# MEGA_MSX.net
KiCad netlist of a schematic drawn in EAGLE
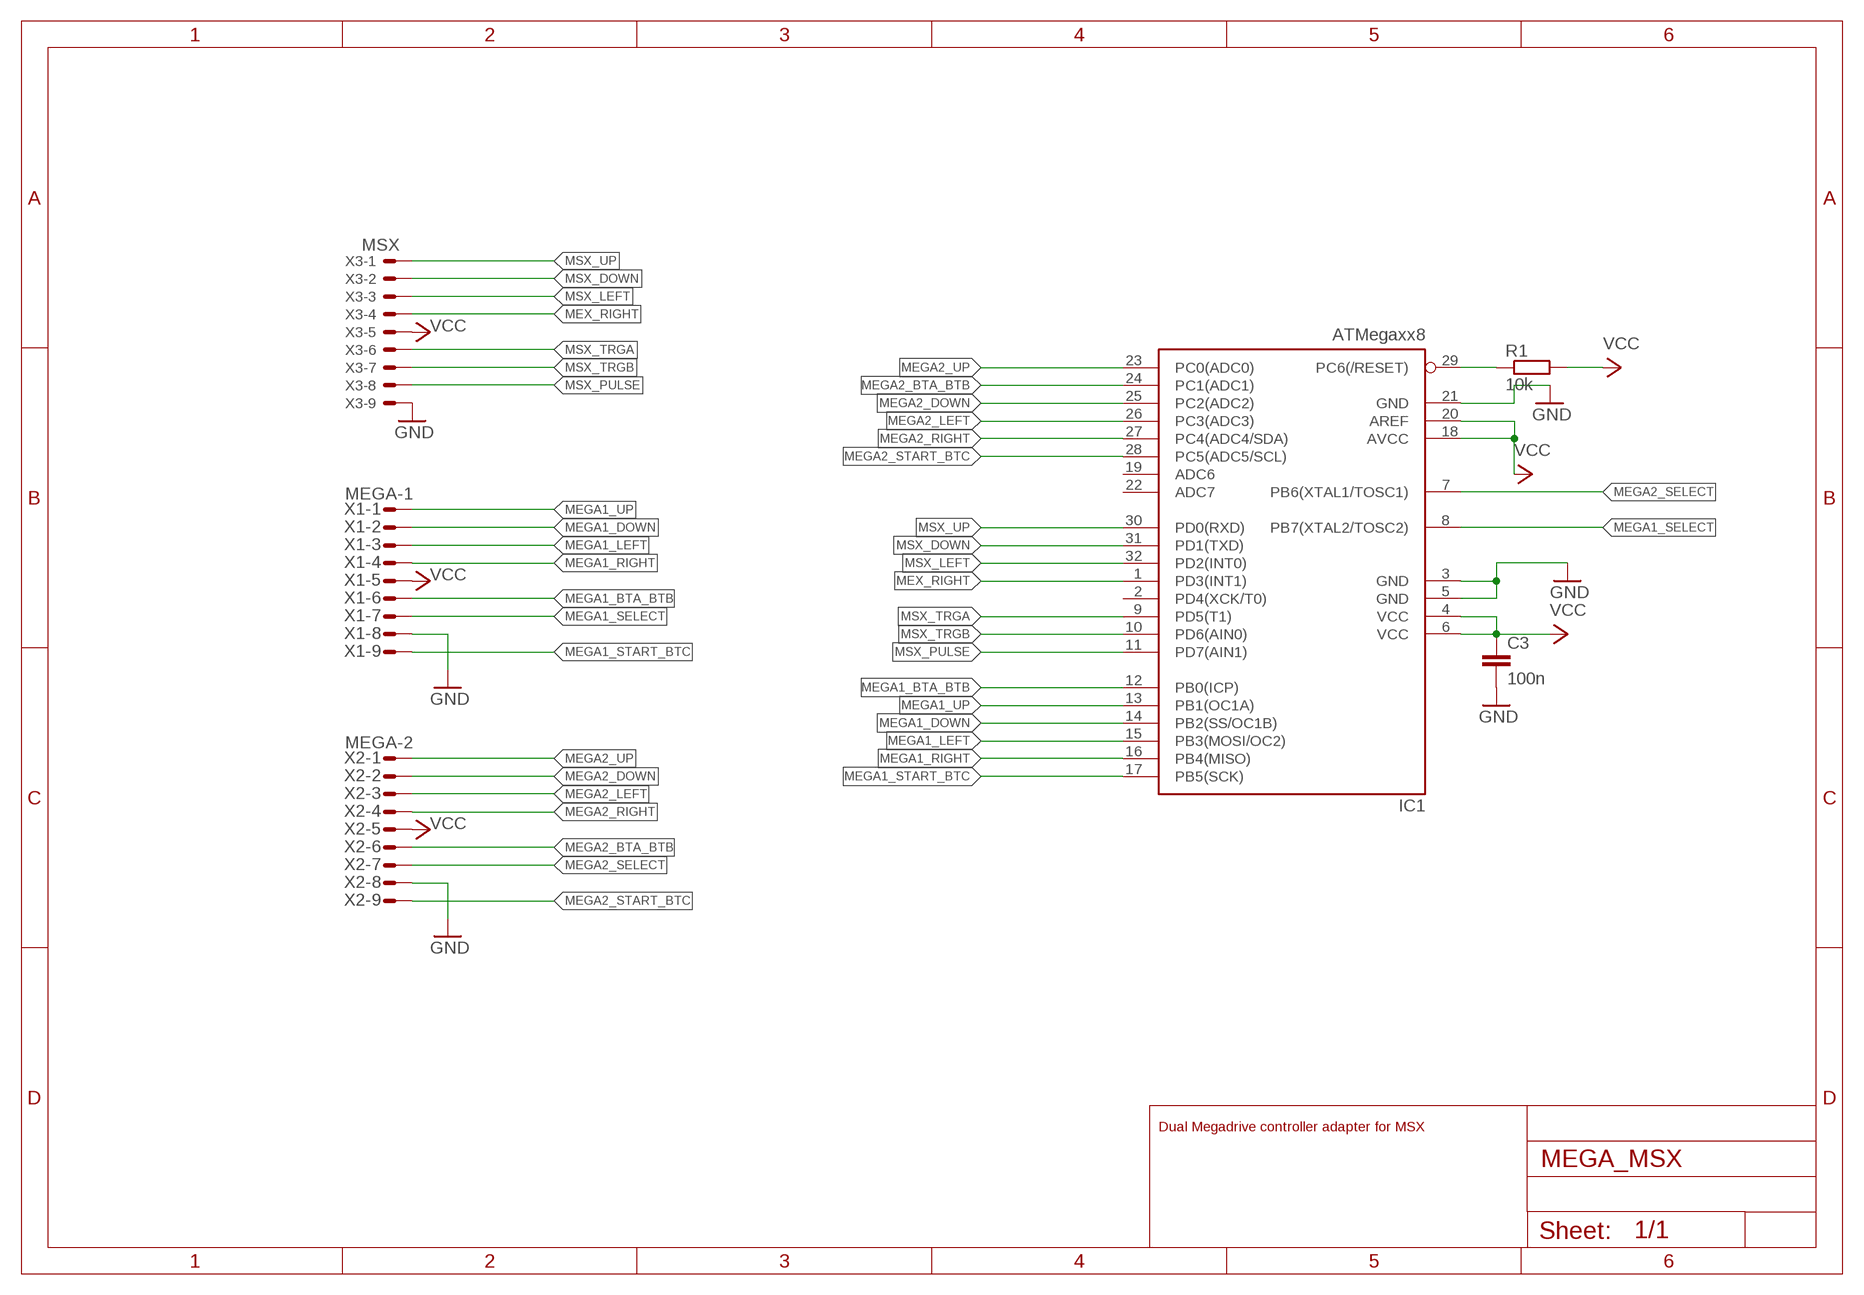
[diagram p0: schematic, sheet 1]

(export (version "E")
  (design (tool "Eeschema 10.0.6"))
  (components
    (comp (ref "C3")
      (value "100n")
      (footprint "eagle-import:C0805")
      (libsource (lib "eagle-import") (part "C-EUC0805"))
    )
    (comp (ref "IC1")
      (value "ATMegaxx8")
      (footprint "eagle-import:TQFP32-08")
      (fields (field (name "MPN") "ATMEGA8-16AU"))
      (libsource (lib "eagle-import") (part "MEGA8-AI"))
    )
    (comp (ref "R1")
      (value "10k")
      (footprint "eagle-import:R0805")
      (libsource (lib "eagle-import") (part "R-EU_R0805"))
    )
    (comp (ref "X1")
      (value "MEGA-1")
      (footprint "eagle-import:M09D")
      (libsource (lib "eagle-import") (part "M09?SD"))
    )
    (comp (ref "X2")
      (value "MEGA-2")
      (footprint "eagle-import:M09D")
      (libsource (lib "eagle-import") (part "M09?SD"))
    )
    (comp (ref "X3")
      (value "MSX")
      (footprint "eagle-import:22-23-2091")
      (fields (field (name "MF") "MOLEX") (field (name "MPN") "22-23-2091"))
      (libsource (lib "eagle-import") (part "22-23-2091"))
    )
  )
  (nets
    (net (code "1") (name "GND") (class "Default")
      (node (ref "C3") (pin "2") (pinfunction "2_2") (pintype "passive"))
      (node (ref "IC1") (pin "21") (pinfunction "GND_21") (pintype "power_in"))
      (node (ref "IC1") (pin "3") (pinfunction "GND_3") (pintype "power_in"))
      (node (ref "IC1") (pin "5") (pinfunction "GND_5") (pintype "power_in"))
      (node (ref "X1") (pin "8") (pinfunction "M_8") (pintype "passive"))
      (node (ref "X2") (pin "8") (pinfunction "M_8") (pintype "passive"))
      (node (ref "X3") (pin "9") (pinfunction "S_9") (pintype "passive"))
    )
    (net (code "2") (name "MEGA1_BTA_BTB") (class "Default")
      (node (ref "IC1") (pin "12") (pinfunction "PB0(ICP)_12") (pintype "bidirectional"))
      (node (ref "X1") (pin "6") (pinfunction "M_6") (pintype "passive"))
    )
    (net (code "3") (name "MEGA1_DOWN") (class "Default")
      (node (ref "IC1") (pin "14") (pinfunction "PB2(SS/OC1B)_14") (pintype "bidirectional"))
      (node (ref "X1") (pin "2") (pinfunction "M_2") (pintype "passive"))
    )
    (net (code "4") (name "MEGA1_LEFT") (class "Default")
      (node (ref "IC1") (pin "15") (pinfunction "PB3(MOSI/OC2)_15") (pintype "bidirectional"))
      (node (ref "X1") (pin "3") (pinfunction "M_3") (pintype "passive"))
    )
    (net (code "5") (name "MEGA1_RIGHT") (class "Default")
      (node (ref "IC1") (pin "16") (pinfunction "PB4(MISO)_16") (pintype "bidirectional"))
      (node (ref "X1") (pin "4") (pinfunction "M_4") (pintype "passive"))
    )
    (net (code "6") (name "MEGA1_SELECT") (class "Default")
      (node (ref "IC1") (pin "8") (pinfunction "PB7(XTAL2/TOSC2)_8") (pintype "bidirectional"))
      (node (ref "X1") (pin "7") (pinfunction "M_7") (pintype "passive"))
    )
    (net (code "7") (name "MEGA1_START_BTC") (class "Default")
      (node (ref "IC1") (pin "17") (pinfunction "PB5(SCK)_17") (pintype "bidirectional"))
      (node (ref "X1") (pin "9") (pinfunction "M_9") (pintype "passive"))
    )
    (net (code "8") (name "MEGA1_UP") (class "Default")
      (node (ref "IC1") (pin "13") (pinfunction "PB1(OC1A)_13") (pintype "bidirectional"))
      (node (ref "X1") (pin "1") (pinfunction "M_1") (pintype "passive"))
    )
    (net (code "9") (name "MEGA2_BTA_BTB") (class "Default")
      (node (ref "IC1") (pin "24") (pinfunction "PC1(ADC1)_24") (pintype "bidirectional"))
      (node (ref "X2") (pin "6") (pinfunction "M_6") (pintype "passive"))
    )
    (net (code "10") (name "MEGA2_DOWN") (class "Default")
      (node (ref "IC1") (pin "25") (pinfunction "PC2(ADC2)_25") (pintype "bidirectional"))
      (node (ref "X2") (pin "2") (pinfunction "M_2") (pintype "passive"))
    )
    (net (code "11") (name "MEGA2_LEFT") (class "Default")
      (node (ref "IC1") (pin "26") (pinfunction "PC3(ADC3)_26") (pintype "bidirectional"))
      (node (ref "X2") (pin "3") (pinfunction "M_3") (pintype "passive"))
    )
    (net (code "12") (name "MEGA2_RIGHT") (class "Default")
      (node (ref "IC1") (pin "27") (pinfunction "PC4(ADC4/SDA)_27") (pintype "bidirectional"))
      (node (ref "X2") (pin "4") (pinfunction "M_4") (pintype "passive"))
    )
    (net (code "13") (name "MEGA2_SELECT") (class "Default")
      (node (ref "IC1") (pin "7") (pinfunction "PB6(XTAL1/TOSC1)_7") (pintype "bidirectional"))
      (node (ref "X2") (pin "7") (pinfunction "M_7") (pintype "passive"))
    )
    (net (code "14") (name "MEGA2_START_BTC") (class "Default")
      (node (ref "IC1") (pin "28") (pinfunction "PC5(ADC5/SCL)_28") (pintype "bidirectional"))
      (node (ref "X2") (pin "9") (pinfunction "M_9") (pintype "passive"))
    )
    (net (code "15") (name "MEGA2_UP") (class "Default")
      (node (ref "IC1") (pin "23") (pinfunction "PC0(ADC0)_23") (pintype "bidirectional"))
      (node (ref "X2") (pin "1") (pinfunction "M_1") (pintype "passive"))
    )
    (net (code "16") (name "MEX_RIGHT") (class "Default")
      (node (ref "IC1") (pin "1") (pinfunction "PD3(INT1)_1") (pintype "bidirectional"))
      (node (ref "X3") (pin "4") (pinfunction "S_4") (pintype "passive"))
    )
    (net (code "17") (name "MSX_DOWN") (class "Default")
      (node (ref "IC1") (pin "31") (pinfunction "PD1(TXD)_31") (pintype "bidirectional"))
      (node (ref "X3") (pin "2") (pinfunction "S_2") (pintype "passive"))
    )
    (net (code "18") (name "MSX_LEFT") (class "Default")
      (node (ref "IC1") (pin "32") (pinfunction "PD2(INT0)_32") (pintype "bidirectional"))
      (node (ref "X3") (pin "3") (pinfunction "S_3") (pintype "passive"))
    )
    (net (code "19") (name "MSX_PULSE") (class "Default")
      (node (ref "IC1") (pin "11") (pinfunction "PD7(AIN1)_11") (pintype "bidirectional"))
      (node (ref "X3") (pin "8") (pinfunction "S_8") (pintype "passive"))
    )
    (net (code "20") (name "MSX_TRGA") (class "Default")
      (node (ref "IC1") (pin "9") (pinfunction "PD5(T1)_9") (pintype "bidirectional"))
      (node (ref "X3") (pin "6") (pinfunction "S_6") (pintype "passive"))
    )
    (net (code "21") (name "MSX_TRGB") (class "Default")
      (node (ref "IC1") (pin "10") (pinfunction "PD6(AIN0)_10") (pintype "bidirectional"))
      (node (ref "X3") (pin "7") (pinfunction "S_7") (pintype "passive"))
    )
    (net (code "22") (name "MSX_UP") (class "Default")
      (node (ref "IC1") (pin "30") (pinfunction "PD0(RXD)_30") (pintype "bidirectional"))
      (node (ref "X3") (pin "1") (pinfunction "S_1") (pintype "passive"))
    )
    (net (code "23") (name "Net-(IC1-PC6({slash}RESET))") (class "Default")
      (node (ref "IC1") (pin "29") (pinfunction "PC6(/RESET)_29") (pintype "bidirectional"))
      (node (ref "R1") (pin "1") (pinfunction "1_1") (pintype "passive"))
    )
    (net (code "24") (name "VCC") (class "Default")
      (node (ref "C3") (pin "1") (pinfunction "1_1") (pintype "passive"))
      (node (ref "IC1") (pin "18") (pinfunction "AVCC_18") (pintype "power_in"))
      (node (ref "IC1") (pin "20") (pinfunction "AREF_20") (pintype "passive"))
      (node (ref "IC1") (pin "4") (pinfunction "VCC_4") (pintype "power_in"))
      (node (ref "IC1") (pin "6") (pinfunction "VCC_6") (pintype "power_in"))
      (node (ref "R1") (pin "2") (pinfunction "2_2") (pintype "passive"))
      (node (ref "X1") (pin "5") (pinfunction "M_5") (pintype "passive"))
      (node (ref "X2") (pin "5") (pinfunction "M_5") (pintype "passive"))
      (node (ref "X3") (pin "5") (pinfunction "S_5") (pintype "passive"))
    )
    (net (code "25") (name "unconnected-(IC1-ADC6-Pad19)") (class "Default")
      (node (ref "IC1") (pin "19") (pinfunction "ADC6_19") (pintype "bidirectional"))
    )
    (net (code "26") (name "unconnected-(IC1-ADC7-Pad22)") (class "Default")
      (node (ref "IC1") (pin "22") (pinfunction "ADC7_22") (pintype "bidirectional"))
    )
    (net (code "27") (name "unconnected-(IC1-PD4(XCK{slash}T0)-Pad2)") (class "Default")
      (node (ref "IC1") (pin "2") (pinfunction "PD4(XCK/T0)_2") (pintype "bidirectional"))
    )
  )
)
